# saha-display.net
KiCad netlist of a schematic drawn in EAGLE
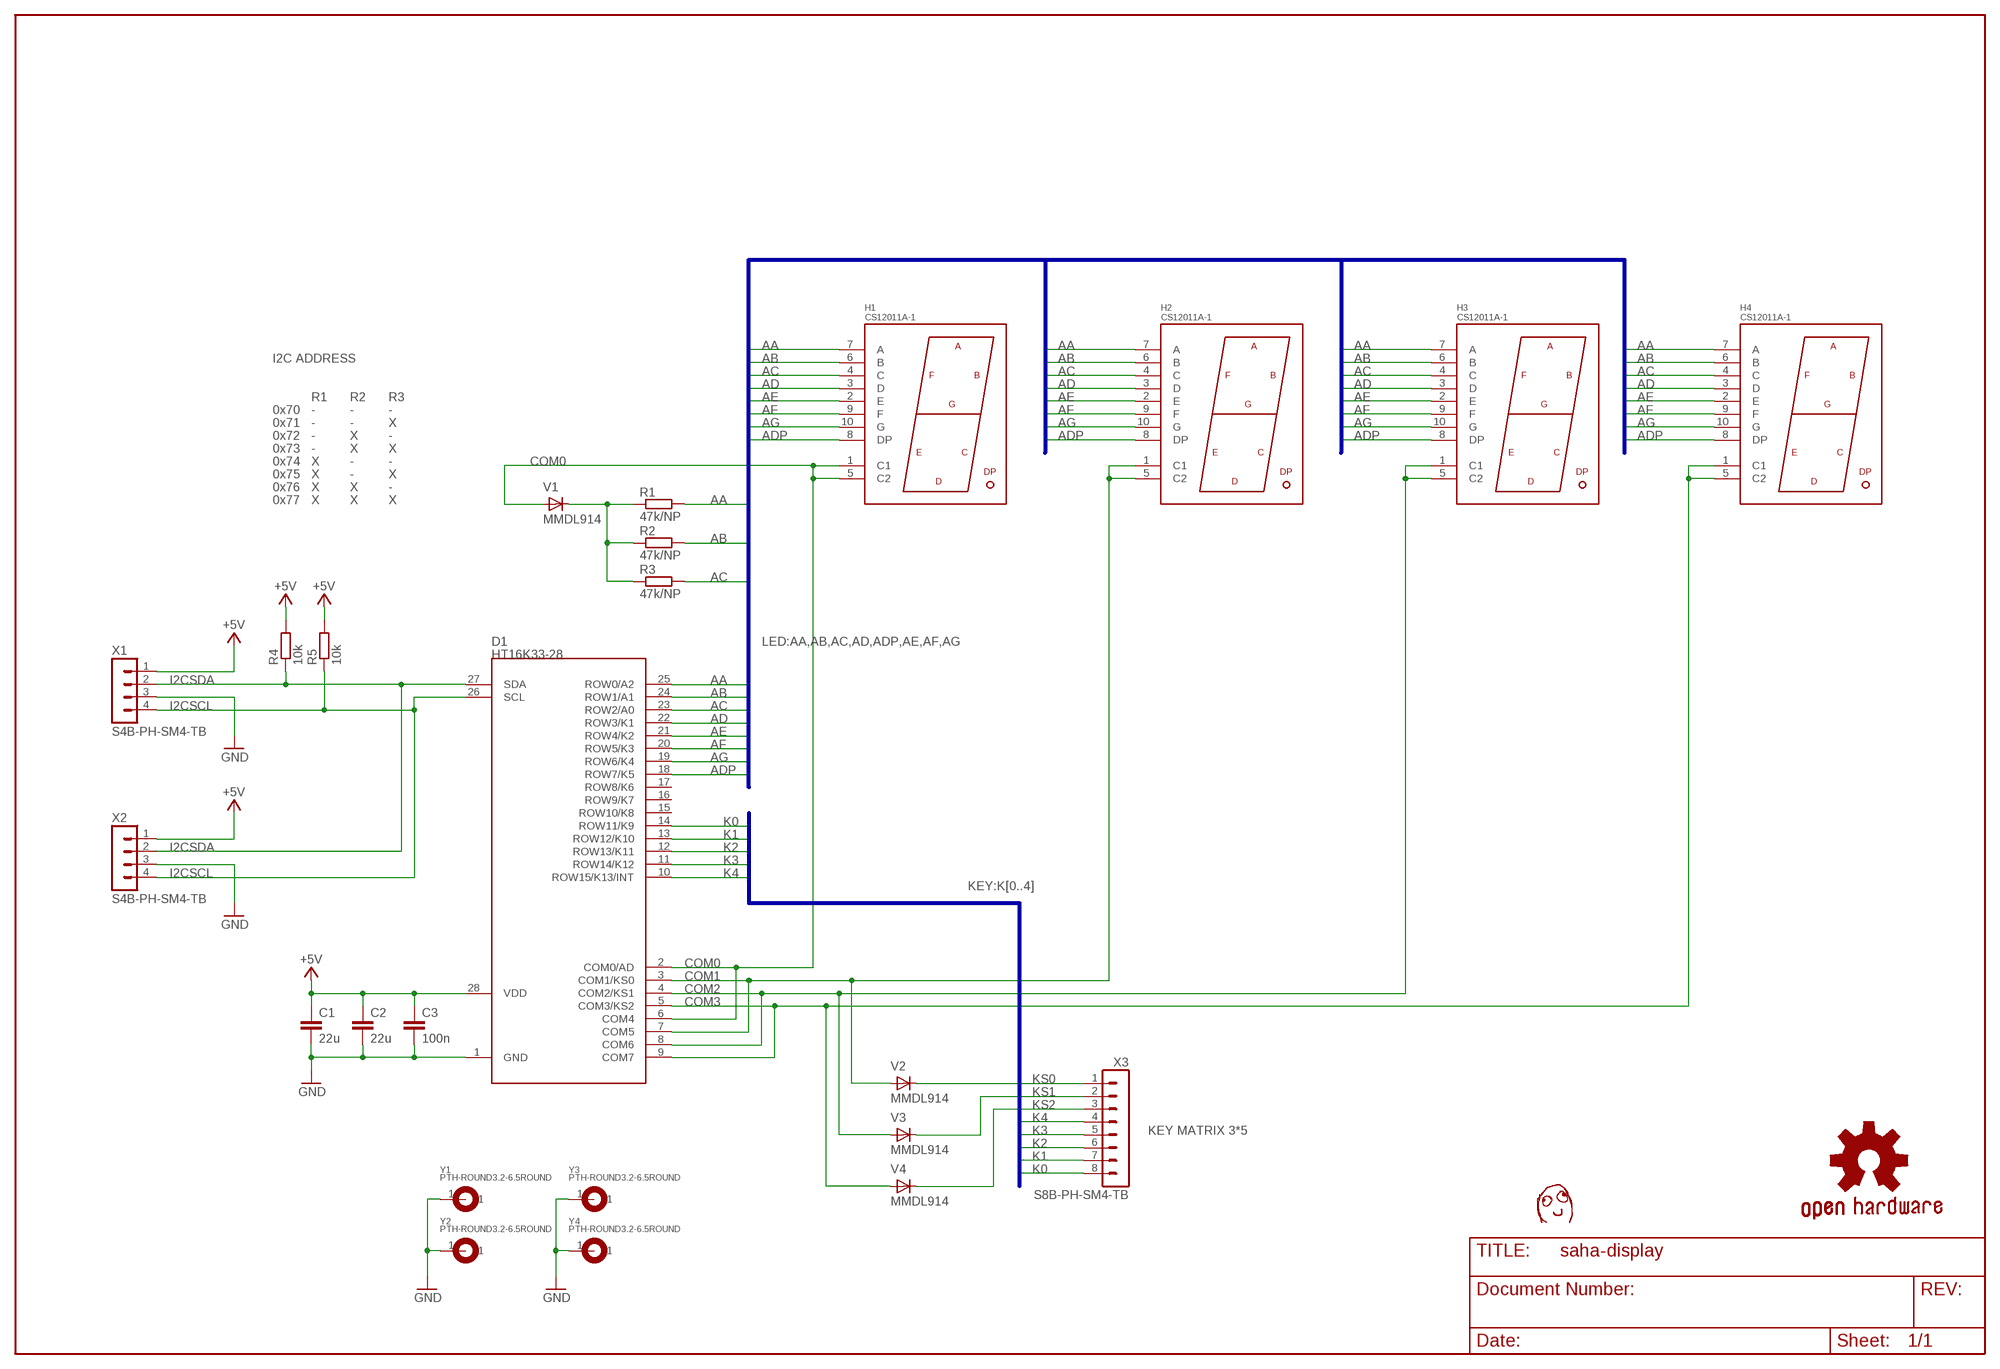
[diagram p0: schematic, sheet 1]

(export (version "E")
  (design (tool "Eeschema 10.0.6"))
  (components
    (comp (ref "C1")
      (value "22u")
      (footprint "eagle-import:C0805")
      (libsource (lib "eagle-import") (part "CAP0805"))
    )
    (comp (ref "C2")
      (value "22u")
      (footprint "eagle-import:C0805")
      (libsource (lib "eagle-import") (part "CAP0805"))
    )
    (comp (ref "C3")
      (value "100n")
      (footprint "eagle-import:C0603")
      (libsource (lib "eagle-import") (part "CAP0603"))
    )
    (comp (ref "D1")
      (value "HT16K33-28")
      (footprint "eagle-import:SOP28-300")
      (libsource (lib "eagle-import") (part "HT16K33-28"))
    )
    (comp (ref "H1")
      (value "CS12011A-1")
      (footprint "eagle-import:7-SEGMENT-1.2INCH")
      (libsource (lib "eagle-import") (part "CS12011A-1"))
    )
    (comp (ref "H2")
      (value "CS12011A-1")
      (footprint "eagle-import:7-SEGMENT-1.2INCH")
      (libsource (lib "eagle-import") (part "CS12011A-1"))
    )
    (comp (ref "H3")
      (value "CS12011A-1")
      (footprint "eagle-import:7-SEGMENT-1.2INCH")
      (libsource (lib "eagle-import") (part "CS12011A-1"))
    )
    (comp (ref "H4")
      (value "CS12011A-1")
      (footprint "eagle-import:7-SEGMENT-1.2INCH")
      (libsource (lib "eagle-import") (part "CS12011A-1"))
    )
    (comp (ref "R1")
      (value "47k/NP")
      (footprint "eagle-import:R0603")
      (libsource (lib "eagle-import") (part "RES0603"))
    )
    (comp (ref "R2")
      (value "47k/NP")
      (footprint "eagle-import:R0603")
      (libsource (lib "eagle-import") (part "RES0603"))
    )
    (comp (ref "R3")
      (value "47k/NP")
      (footprint "eagle-import:R0603")
      (libsource (lib "eagle-import") (part "RES0603"))
    )
    (comp (ref "R4")
      (value "10k")
      (footprint "eagle-import:R0603")
      (libsource (lib "eagle-import") (part "RES0603"))
    )
    (comp (ref "R5")
      (value "10k")
      (footprint "eagle-import:R0603")
      (libsource (lib "eagle-import") (part "RES0603"))
    )
    (comp (ref "U$1")
      (value "DAFUG")
      (footprint "eagle-import:DAFUG")
      (libsource (lib "eagle-import") (part "DAFUG"))
    )
    (comp (ref "V1")
      (value "MMDL914")
      (footprint "eagle-import:SOD-323")
      (libsource (lib "eagle-import") (part "MMDL914"))
    )
    (comp (ref "V2")
      (value "MMDL914")
      (footprint "eagle-import:SOD-323")
      (libsource (lib "eagle-import") (part "MMDL914"))
    )
    (comp (ref "V3")
      (value "MMDL914")
      (footprint "eagle-import:SOD-323")
      (libsource (lib "eagle-import") (part "MMDL914"))
    )
    (comp (ref "V4")
      (value "MMDL914")
      (footprint "eagle-import:SOD-323")
      (libsource (lib "eagle-import") (part "MMDL914"))
    )
    (comp (ref "X1")
      (value "S4B-PH-SM4-TB")
      (footprint "eagle-import:JST-PH2.0-RA-4")
      (libsource (lib "eagle-import") (part "S4B-PH-SM4-TB"))
    )
    (comp (ref "X2")
      (value "S4B-PH-SM4-TB")
      (footprint "eagle-import:JST-PH2.0-RA-4")
      (libsource (lib "eagle-import") (part "S4B-PH-SM4-TB"))
    )
    (comp (ref "X3")
      (value "S8B-PH-SM4-TB")
      (footprint "eagle-import:JST-PH2.0-RA-8")
      (libsource (lib "eagle-import") (part "S8B-PH-SM4-TB"))
    )
    (comp (ref "Y1")
      (value "PTH-ROUND3.2-6.5ROUND")
      (footprint "eagle-import:EKE_PTH-3.2-6.5")
      (libsource (lib "eagle-import") (part "PTH-ROUND3.2-6.5ROUND"))
    )
    (comp (ref "Y2")
      (value "PTH-ROUND3.2-6.5ROUND")
      (footprint "eagle-import:EKE_PTH-3.2-6.5")
      (libsource (lib "eagle-import") (part "PTH-ROUND3.2-6.5ROUND"))
    )
    (comp (ref "Y3")
      (value "PTH-ROUND3.2-6.5ROUND")
      (footprint "eagle-import:EKE_PTH-3.2-6.5")
      (libsource (lib "eagle-import") (part "PTH-ROUND3.2-6.5ROUND"))
    )
    (comp (ref "Y4")
      (value "PTH-ROUND3.2-6.5ROUND")
      (footprint "eagle-import:EKE_PTH-3.2-6.5")
      (libsource (lib "eagle-import") (part "PTH-ROUND3.2-6.5ROUND"))
    )
  )
  (nets
    (net (code "7") (name "+5V") (class "Default")
      (node (ref "C1") (pin "1") (pinfunction "1_1") (pintype "passive"))
      (node (ref "C2") (pin "1") (pinfunction "1_1") (pintype "passive"))
      (node (ref "C3") (pin "1") (pinfunction "1_1") (pintype "passive"))
      (node (ref "D1") (pin "28") (pinfunction "VDD_28") (pintype "bidirectional"))
      (node (ref "R4") (pin "2") (pinfunction "2_2") (pintype "passive"))
      (node (ref "R5") (pin "2") (pinfunction "2_2") (pintype "passive"))
      (node (ref "X1") (pin "1") (pinfunction "1_1") (pintype "passive"))
      (node (ref "X2") (pin "1") (pinfunction "1_1") (pintype "passive"))
    )
    (net (code "8") (name "/AA") (class "Default")
      (node (ref "D1") (pin "25") (pinfunction "ROW0/A2_25") (pintype "bidirectional"))
      (node (ref "H1") (pin "7") (pinfunction "A_7") (pintype "bidirectional"))
      (node (ref "H2") (pin "7") (pinfunction "A_7") (pintype "bidirectional"))
      (node (ref "H3") (pin "7") (pinfunction "A_7") (pintype "bidirectional"))
      (node (ref "H4") (pin "7") (pinfunction "A_7") (pintype "bidirectional"))
      (node (ref "R1") (pin "2") (pinfunction "2_2") (pintype "passive"))
    )
    (net (code "9") (name "/AB") (class "Default")
      (node (ref "D1") (pin "24") (pinfunction "ROW1/A1_24") (pintype "bidirectional"))
      (node (ref "H1") (pin "6") (pinfunction "B_6") (pintype "bidirectional"))
      (node (ref "H2") (pin "6") (pinfunction "B_6") (pintype "bidirectional"))
      (node (ref "H3") (pin "6") (pinfunction "B_6") (pintype "bidirectional"))
      (node (ref "H4") (pin "6") (pinfunction "B_6") (pintype "bidirectional"))
      (node (ref "R2") (pin "2") (pinfunction "2_2") (pintype "passive"))
    )
    (net (code "10") (name "/AC") (class "Default")
      (node (ref "D1") (pin "23") (pinfunction "ROW2/A0_23") (pintype "bidirectional"))
      (node (ref "H1") (pin "4") (pinfunction "C_4") (pintype "bidirectional"))
      (node (ref "H2") (pin "4") (pinfunction "C_4") (pintype "bidirectional"))
      (node (ref "H3") (pin "4") (pinfunction "C_4") (pintype "bidirectional"))
      (node (ref "H4") (pin "4") (pinfunction "C_4") (pintype "bidirectional"))
      (node (ref "R3") (pin "2") (pinfunction "2_2") (pintype "passive"))
    )
    (net (code "11") (name "/AD") (class "Default")
      (node (ref "D1") (pin "22") (pinfunction "ROW3/K1_22") (pintype "bidirectional"))
      (node (ref "H1") (pin "3") (pinfunction "D_3") (pintype "bidirectional"))
      (node (ref "H2") (pin "3") (pinfunction "D_3") (pintype "bidirectional"))
      (node (ref "H3") (pin "3") (pinfunction "D_3") (pintype "bidirectional"))
      (node (ref "H4") (pin "3") (pinfunction "D_3") (pintype "bidirectional"))
    )
    (net (code "12") (name "/ADP") (class "Default")
      (node (ref "D1") (pin "18") (pinfunction "ROW7/K5_18") (pintype "bidirectional"))
      (node (ref "H1") (pin "8") (pinfunction "DP_8") (pintype "bidirectional"))
      (node (ref "H2") (pin "8") (pinfunction "DP_8") (pintype "bidirectional"))
      (node (ref "H3") (pin "8") (pinfunction "DP_8") (pintype "bidirectional"))
      (node (ref "H4") (pin "8") (pinfunction "DP_8") (pintype "bidirectional"))
    )
    (net (code "13") (name "/AE") (class "Default")
      (node (ref "D1") (pin "21") (pinfunction "ROW4/K2_21") (pintype "bidirectional"))
      (node (ref "H1") (pin "2") (pinfunction "E_2") (pintype "bidirectional"))
      (node (ref "H2") (pin "2") (pinfunction "E_2") (pintype "bidirectional"))
      (node (ref "H3") (pin "2") (pinfunction "E_2") (pintype "bidirectional"))
      (node (ref "H4") (pin "2") (pinfunction "E_2") (pintype "bidirectional"))
    )
    (net (code "14") (name "/AF") (class "Default")
      (node (ref "D1") (pin "20") (pinfunction "ROW5/K3_20") (pintype "bidirectional"))
      (node (ref "H1") (pin "9") (pinfunction "F_9") (pintype "bidirectional"))
      (node (ref "H2") (pin "9") (pinfunction "F_9") (pintype "bidirectional"))
      (node (ref "H3") (pin "9") (pinfunction "F_9") (pintype "bidirectional"))
      (node (ref "H4") (pin "9") (pinfunction "F_9") (pintype "bidirectional"))
    )
    (net (code "15") (name "/AG") (class "Default")
      (node (ref "D1") (pin "19") (pinfunction "ROW6/K4_19") (pintype "bidirectional"))
      (node (ref "H1") (pin "10") (pinfunction "G_10") (pintype "bidirectional"))
      (node (ref "H2") (pin "10") (pinfunction "G_10") (pintype "bidirectional"))
      (node (ref "H3") (pin "10") (pinfunction "G_10") (pintype "bidirectional"))
      (node (ref "H4") (pin "10") (pinfunction "G_10") (pintype "bidirectional"))
    )
    (net (code "16") (name "/COM0") (class "Default")
      (node (ref "D1") (pin "2") (pinfunction "COM0/AD_2") (pintype "bidirectional"))
      (node (ref "D1") (pin "6") (pinfunction "COM4_6") (pintype "bidirectional"))
      (node (ref "H1") (pin "1") (pinfunction "C1_1") (pintype "bidirectional"))
      (node (ref "H1") (pin "5") (pinfunction "C2_5") (pintype "bidirectional"))
      (node (ref "V1") (pin "A") (pinfunction "A_A") (pintype "passive"))
    )
    (net (code "17") (name "/COM1") (class "Default")
      (node (ref "D1") (pin "3") (pinfunction "COM1/KS0_3") (pintype "bidirectional"))
      (node (ref "D1") (pin "7") (pinfunction "COM5_7") (pintype "bidirectional"))
      (node (ref "H2") (pin "1") (pinfunction "C1_1") (pintype "bidirectional"))
      (node (ref "H2") (pin "5") (pinfunction "C2_5") (pintype "bidirectional"))
      (node (ref "V2") (pin "A") (pinfunction "A_A") (pintype "passive"))
    )
    (net (code "18") (name "/COM2") (class "Default")
      (node (ref "D1") (pin "4") (pinfunction "COM2/KS1_4") (pintype "bidirectional"))
      (node (ref "D1") (pin "8") (pinfunction "COM6_8") (pintype "bidirectional"))
      (node (ref "H3") (pin "1") (pinfunction "C1_1") (pintype "bidirectional"))
      (node (ref "H3") (pin "5") (pinfunction "C2_5") (pintype "bidirectional"))
      (node (ref "V3") (pin "A") (pinfunction "A_A") (pintype "passive"))
    )
    (net (code "19") (name "/COM3") (class "Default")
      (node (ref "D1") (pin "5") (pinfunction "COM3/KS2_5") (pintype "bidirectional"))
      (node (ref "D1") (pin "9") (pinfunction "COM7_9") (pintype "bidirectional"))
      (node (ref "H4") (pin "1") (pinfunction "C1_1") (pintype "bidirectional"))
      (node (ref "H4") (pin "5") (pinfunction "C2_5") (pintype "bidirectional"))
      (node (ref "V4") (pin "A") (pinfunction "A_A") (pintype "passive"))
    )
    (net (code "20") (name "/I2CSCL") (class "Default")
      (node (ref "D1") (pin "26") (pinfunction "SCL_26") (pintype "bidirectional"))
      (node (ref "R5") (pin "1") (pinfunction "1_1") (pintype "passive"))
      (node (ref "X1") (pin "4") (pinfunction "4_4") (pintype "passive"))
      (node (ref "X2") (pin "4") (pinfunction "4_4") (pintype "passive"))
    )
    (net (code "21") (name "/I2CSDA") (class "Default")
      (node (ref "D1") (pin "27") (pinfunction "SDA_27") (pintype "bidirectional"))
      (node (ref "R4") (pin "1") (pinfunction "1_1") (pintype "passive"))
      (node (ref "X1") (pin "2") (pinfunction "2_2") (pintype "passive"))
      (node (ref "X2") (pin "2") (pinfunction "2_2") (pintype "passive"))
    )
    (net (code "22") (name "/K0") (class "Default")
      (node (ref "D1") (pin "14") (pinfunction "ROW11/K9_14") (pintype "bidirectional"))
      (node (ref "X3") (pin "8") (pinfunction "8_8") (pintype "passive"))
    )
    (net (code "23") (name "/K1") (class "Default")
      (node (ref "D1") (pin "13") (pinfunction "ROW12/K10_13") (pintype "bidirectional"))
      (node (ref "X3") (pin "7") (pinfunction "7_7") (pintype "passive"))
    )
    (net (code "24") (name "/K2") (class "Default")
      (node (ref "D1") (pin "12") (pinfunction "ROW13/K11_12") (pintype "bidirectional"))
      (node (ref "X3") (pin "6") (pinfunction "6_6") (pintype "passive"))
    )
    (net (code "25") (name "/K3") (class "Default")
      (node (ref "D1") (pin "11") (pinfunction "ROW14/K12_11") (pintype "bidirectional"))
      (node (ref "X3") (pin "5") (pinfunction "5_5") (pintype "passive"))
    )
    (net (code "26") (name "/K4") (class "Default")
      (node (ref "D1") (pin "10") (pinfunction "ROW15/K13/INT_10") (pintype "bidirectional"))
      (node (ref "X3") (pin "4") (pinfunction "4_4") (pintype "passive"))
    )
    (net (code "28") (name "/KS0") (class "Default")
      (node (ref "V2") (pin "C") (pinfunction "C_C") (pintype "passive"))
      (node (ref "X3") (pin "1") (pinfunction "1_1") (pintype "passive"))
    )
    (net (code "29") (name "/KS1") (class "Default")
      (node (ref "V3") (pin "C") (pinfunction "C_C") (pintype "passive"))
      (node (ref "X3") (pin "2") (pinfunction "2_2") (pintype "passive"))
    )
    (net (code "30") (name "/KS2") (class "Default")
      (node (ref "V4") (pin "C") (pinfunction "C_C") (pintype "passive"))
      (node (ref "X3") (pin "3") (pinfunction "3_3") (pintype "passive"))
    )
    (net (code "32") (name "GND") (class "Default")
      (node (ref "C1") (pin "2") (pinfunction "2_2") (pintype "passive"))
      (node (ref "C2") (pin "2") (pinfunction "2_2") (pintype "passive"))
      (node (ref "C3") (pin "2") (pinfunction "2_2") (pintype "passive"))
      (node (ref "D1") (pin "1") (pinfunction "GND_1") (pintype "bidirectional"))
      (node (ref "X1") (pin "3") (pinfunction "3_3") (pintype "passive"))
      (node (ref "X2") (pin "3") (pinfunction "3_3") (pintype "passive"))
      (node (ref "Y1") (pin "1") (pinfunction "1_1") (pintype "bidirectional"))
      (node (ref "Y2") (pin "1") (pinfunction "1_1") (pintype "bidirectional"))
      (node (ref "Y3") (pin "1") (pinfunction "1_1") (pintype "bidirectional"))
      (node (ref "Y4") (pin "1") (pinfunction "1_1") (pintype "bidirectional"))
    )
    (net (code "33") (name "Net-(R1-Pad1)") (class "Default")
      (node (ref "R1") (pin "1") (pinfunction "1_1") (pintype "passive"))
      (node (ref "R2") (pin "1") (pinfunction "1_1") (pintype "passive"))
      (node (ref "R3") (pin "1") (pinfunction "1_1") (pintype "passive"))
      (node (ref "V1") (pin "C") (pinfunction "C_C") (pintype "passive"))
    )
    (net (code "34") (name "unconnected-(D1-ROW8{slash}K6-Pad17)") (class "Default")
      (node (ref "D1") (pin "17") (pinfunction "ROW8/K6_17") (pintype "bidirectional"))
    )
    (net (code "35") (name "unconnected-(D1-ROW9{slash}K7-Pad16)") (class "Default")
      (node (ref "D1") (pin "16") (pinfunction "ROW9/K7_16") (pintype "bidirectional"))
    )
    (net (code "36") (name "unconnected-(D1-ROW10{slash}K8-Pad15)") (class "Default")
      (node (ref "D1") (pin "15") (pinfunction "ROW10/K8_15") (pintype "bidirectional"))
    )
  )
)
